# Button_Board.net
KiCad netlist of a schematic drawn in EAGLE
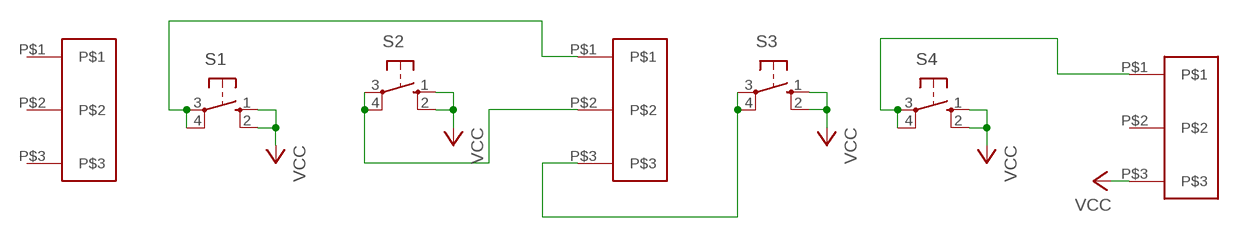
[diagram p0: schematic, sheet 1]

(export (version "E")
  (design (tool "Eeschema 10.0.6"))
  (components
    (comp (ref "S1")
      (value "40-XX")
      (footprint "eagle-import:B3F-40XX")
      (fields (field (name "MF") "OMRON COMPONENTS USA") (field (name "MPN") "B3F-4000"))
      (libsource (lib "eagle-import") (part "40-XX"))
    )
    (comp (ref "S2")
      (value "40-XX")
      (footprint "eagle-import:B3F-40XX")
      (fields (field (name "MF") "OMRON COMPONENTS USA") (field (name "MPN") "B3F-4000"))
      (libsource (lib "eagle-import") (part "40-XX"))
    )
    (comp (ref "S3")
      (value "40-XX")
      (footprint "eagle-import:B3F-40XX")
      (fields (field (name "MF") "OMRON COMPONENTS USA") (field (name "MPN") "B3F-4000"))
      (libsource (lib "eagle-import") (part "40-XX"))
    )
    (comp (ref "S4")
      (value "40-XX")
      (footprint "eagle-import:B3F-40XX")
      (fields (field (name "MF") "OMRON COMPONENTS USA") (field (name "MPN") "B3F-4000"))
      (libsource (lib "eagle-import") (part "40-XX"))
    )
    (comp (ref "U$1")
      (value "3_PIN_FEMALE_HEADER")
      (footprint "eagle-import:3_PIN_FEMALE_HEADER")
      (libsource (lib "eagle-import") (part "3_PIN_FEMALE_HEADER"))
    )
    (comp (ref "U$2")
      (value "3_PIN_FEMALE_HEADER")
      (footprint "eagle-import:3_PIN_FEMALE_HEADER")
      (libsource (lib "eagle-import") (part "3_PIN_FEMALE_HEADER"))
    )
    (comp (ref "U$3")
      (value "3_PIN_FEMALE_HEADER")
      (footprint "eagle-import:3_PIN_FEMALE_HEADER")
      (libsource (lib "eagle-import") (part "3_PIN_FEMALE_HEADER"))
    )
  )
  (nets
    (net (code "1") (name "Net-(S1-P)") (class "Default")
      (node (ref "S1") (pin "3") (pinfunction "P_3") (pintype "passive"))
      (node (ref "S1") (pin "4") (pinfunction "P1_4") (pintype "passive"))
      (node (ref "U$2") (pin "P$1") (pinfunction "P$1_P$1") (pintype "bidirectional"))
    )
    (net (code "2") (name "Net-(S2-P)") (class "Default")
      (node (ref "S2") (pin "3") (pinfunction "P_3") (pintype "passive"))
      (node (ref "S2") (pin "4") (pinfunction "P1_4") (pintype "passive"))
      (node (ref "U$2") (pin "P$2") (pinfunction "P$2_P$2") (pintype "bidirectional"))
    )
    (net (code "3") (name "Net-(S3-P)") (class "Default")
      (node (ref "S3") (pin "3") (pinfunction "P_3") (pintype "passive"))
      (node (ref "S3") (pin "4") (pinfunction "P1_4") (pintype "passive"))
      (node (ref "U$2") (pin "P$3") (pinfunction "P$3_P$3") (pintype "bidirectional"))
    )
    (net (code "4") (name "Net-(S4-P)") (class "Default")
      (node (ref "S4") (pin "3") (pinfunction "P_3") (pintype "passive"))
      (node (ref "S4") (pin "4") (pinfunction "P1_4") (pintype "passive"))
      (node (ref "U$3") (pin "P$1") (pinfunction "P$1_P$1") (pintype "bidirectional"))
    )
    (net (code "5") (name "VCC") (class "Default")
      (node (ref "S1") (pin "1") (pinfunction "S_1") (pintype "passive"))
      (node (ref "S1") (pin "2") (pinfunction "S1_2") (pintype "passive"))
      (node (ref "S2") (pin "1") (pinfunction "S_1") (pintype "passive"))
      (node (ref "S2") (pin "2") (pinfunction "S1_2") (pintype "passive"))
      (node (ref "S3") (pin "1") (pinfunction "S_1") (pintype "passive"))
      (node (ref "S3") (pin "2") (pinfunction "S1_2") (pintype "passive"))
      (node (ref "S4") (pin "1") (pinfunction "S_1") (pintype "passive"))
      (node (ref "S4") (pin "2") (pinfunction "S1_2") (pintype "passive"))
      (node (ref "U$3") (pin "P$3") (pinfunction "P$3_P$3") (pintype "bidirectional"))
    )
    (net (code "6") (name "unconnected-(U$1-PadP$1)") (class "Default")
      (node (ref "U$1") (pin "P$1") (pinfunction "P$1_P$1") (pintype "bidirectional"))
    )
    (net (code "7") (name "unconnected-(U$1-PadP$2)") (class "Default")
      (node (ref "U$1") (pin "P$2") (pinfunction "P$2_P$2") (pintype "bidirectional"))
    )
    (net (code "8") (name "unconnected-(U$1-PadP$3)") (class "Default")
      (node (ref "U$1") (pin "P$3") (pinfunction "P$3_P$3") (pintype "bidirectional"))
    )
    (net (code "9") (name "unconnected-(U$3-PadP$2)") (class "Default")
      (node (ref "U$3") (pin "P$2") (pinfunction "P$2_P$2") (pintype "bidirectional"))
    )
  )
)
